# SmallStm.net
KiCad netlist of a schematic drawn in EasyEDA Pro
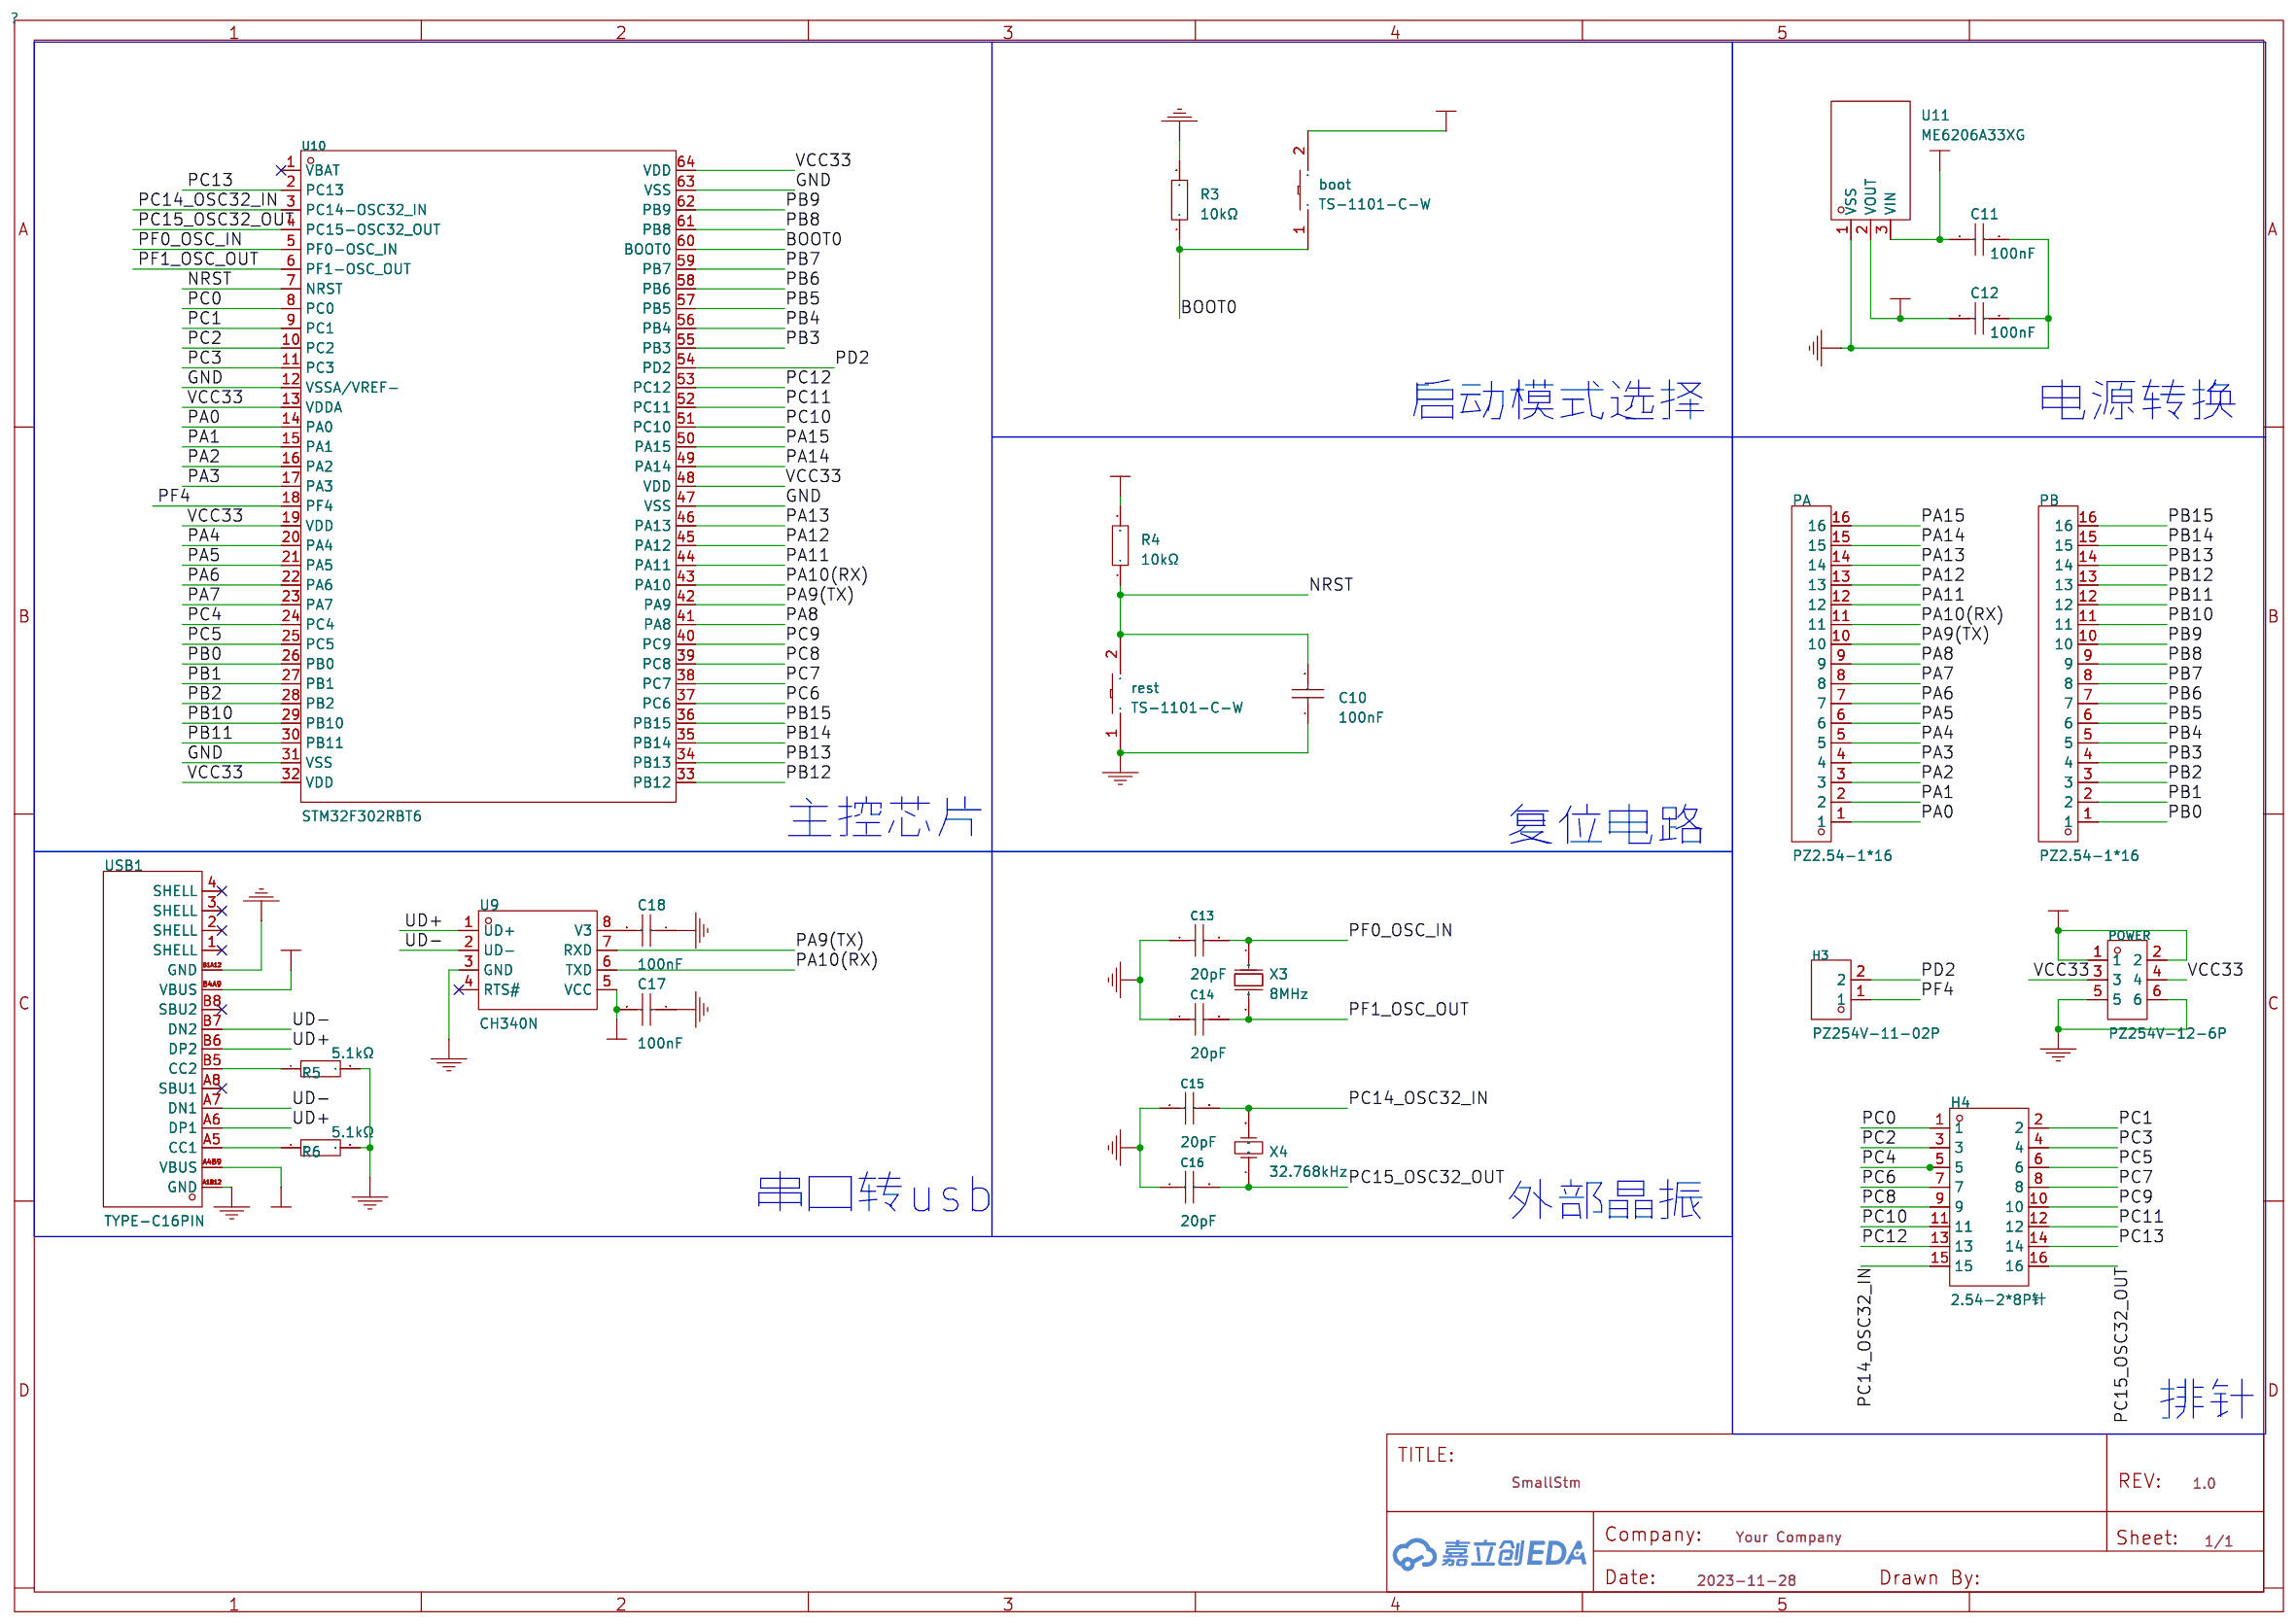
[diagram p0: schematic sheet]

(export (version "E")
  (design (tool "Eeschema 10.0.6"))
  (components
    (comp (ref "boot")
      (value "TS-1101-C-W")
      (footprint "easyedapro:SW-SMD_L6.0-W3.3-LS8.0")
      (description "电路结构:单刀单掷;带支架:否;触点电流:50mA;额定电压(AC):-;额定电压(DC):12V;额定功率:-;安装方式:立贴;绝缘电阻:-;带灯:无;作用力:260gf;机械寿命:5万次;")
      (fields (field (name "Manufacturer") "XKB Connectivity(中国星坤)"))
      (libsource (lib "easyedapro") (part "TS-1101-C-W"))
    )
    (comp (ref "C10")
      (value "100nF")
      (footprint "easyedapro:C0603")
      (description "容值:100nF;精度:±10%;额定电压:50V;材质(温度系数):X7R;")
      (fields (field (name "Manufacturer Part") "0603B104K500NT") (field (name "Manufacturer") "FH(风华)"))
      (libsource (lib "easyedapro") (part "0603B104K500NT"))
    )
    (comp (ref "C11")
      (value "100nF")
      (footprint "easyedapro:C0805")
      (description "容值:100nF;精度:±10%;额定电压:50V;材质(温度系数):X7R;")
      (fields (field (name "Manufacturer Part") "0805B104K500NT") (field (name "Manufacturer") "FH(风华)"))
      (libsource (lib "easyedapro") (part "0805B104K500NT"))
    )
    (comp (ref "C12")
      (value "100nF")
      (footprint "easyedapro:C0805")
      (description "容值:100nF;精度:±10%;额定电压:50V;材质(温度系数):X7R;")
      (fields (field (name "Manufacturer Part") "0805B104K500NT") (field (name "Manufacturer") "FH(风华)"))
      (libsource (lib "easyedapro") (part "0805B104K500NT"))
    )
    (comp (ref "C13")
      (value "20pF")
      (footprint "easyedapro:C0402")
      (description "容值:20pF;精度:±5%;额定电压:50V;材质(温度系数):C0G;")
      (fields (field (name "Manufacturer Part") "0402CG200J500NT") (field (name "Manufacturer") "FH(风华)"))
      (libsource (lib "easyedapro") (part "0402CG200J500NT"))
    )
    (comp (ref "C14")
      (value "20pF")
      (footprint "easyedapro:C0402")
      (description "容值:20pF;精度:±5%;额定电压:50V;材质(温度系数):C0G;")
      (fields (field (name "Manufacturer Part") "0402CG200J500NT") (field (name "Manufacturer") "FH(风华)"))
      (libsource (lib "easyedapro") (part "0402CG200J500NT"))
    )
    (comp (ref "C15")
      (value "20pF")
      (footprint "easyedapro:C0402")
      (description "容值:20pF;精度:±5%;额定电压:50V;材质(温度系数):C0G;")
      (fields (field (name "Manufacturer Part") "0402CG200J500NT") (field (name "Manufacturer") "FH(风华)"))
      (libsource (lib "easyedapro") (part "0402CG200J500NT"))
    )
    (comp (ref "C16")
      (value "20pF")
      (footprint "easyedapro:C0402")
      (description "容值:20pF;精度:±5%;额定电压:50V;材质(温度系数):C0G;")
      (fields (field (name "Manufacturer Part") "0402CG200J500NT") (field (name "Manufacturer") "FH(风华)"))
      (libsource (lib "easyedapro") (part "0402CG200J500NT"))
    )
    (comp (ref "C17")
      (value "100nF")
      (footprint "easyedapro:C0603")
      (description "容值:100nF;精度:±10%;额定电压:50V;材质(温度系数):X7R;")
      (fields (field (name "Manufacturer Part") "0603B104K500NT") (field (name "Manufacturer") "FH(风华)"))
      (libsource (lib "easyedapro") (part "0603B104K500NT"))
    )
    (comp (ref "C18")
      (value "100nF")
      (footprint "easyedapro:C0603")
      (description "容值:100nF;精度:±10%;额定电压:50V;材质(温度系数):X7R;")
      (fields (field (name "Manufacturer Part") "0603B104K500NT") (field (name "Manufacturer") "FH(风华)"))
      (libsource (lib "easyedapro") (part "0603B104K500NT"))
    )
    (comp (ref "H3")
      (value "PZ254V-11-02P")
      (footprint "easyedapro:HDR-TH_2P-P2.54-V-M")
      (fields (field (name "Manufacturer") "XFCN(兴飞)"))
      (libsource (lib "easyedapro") (part "PZ254V-11-02P"))
    )
    (comp (ref "H4")
      (value "2.54-2*8P针")
      (footprint "easyedapro:HDR-TH_16P-P2.54-V-M-R2-C8-S2.54")
      (description "圆针/方针:-;额定电流:-;额定电压:-;配合针长度:-;塑高:-;触头材质:-;")
      (fields (field (name "Manufacturer") "BOOMELE(博穆精密)"))
      (libsource (lib "easyedapro") (part "2.54-2*8P针"))
    )
    (comp (ref "PA")
      (value "PZ2.54-1*16")
      (footprint "easyedapro:HDR-TH_16P-P2.54-V-M")
      (fields (field (name "Manufacturer") "ZHOURI(洲日)"))
      (libsource (lib "easyedapro") (part "PZ2.54-1*16"))
    )
    (comp (ref "PB")
      (value "PZ2.54-1*16")
      (footprint "easyedapro:HDR-TH_16P-P2.54-V-M")
      (fields (field (name "Manufacturer") "ZHOURI(洲日)"))
      (libsource (lib "easyedapro") (part "PZ2.54-1*16"))
    )
    (comp (ref "POWER")
      (value "PZ254V-12-6P")
      (footprint "easyedapro:HDR-TH_6P-P2.54-V-M-R2-C3-S2.54")
      (fields (field (name "Manufacturer") "XFCN(兴飞)"))
      (libsource (lib "easyedapro") (part "PZ254V-12-6P"))
    )
    (comp (ref "R3")
      (value "10kΩ")
      (footprint "easyedapro:R0603")
      (description "阻值:10kΩ;精度:±1%;功率:100mW;温度系数:±100ppm/°C;电阻类型:厚膜电阻;")
      (fields
        (field (name "Manufacturer Part") "0603WAF1002T5E")
        (field (name "Manufacturer") "UNI-ROYAL(厚声)")
      )
      (libsource (lib "easyedapro") (part "0603WAF1002T5E"))
    )
    (comp (ref "R4")
      (value "10kΩ")
      (footprint "easyedapro:R0603")
      (description "阻值:10kΩ;精度:±1%;功率:100mW;温度系数:±100ppm/°C;电阻类型:厚膜电阻;")
      (fields
        (field (name "Manufacturer Part") "0603WAF1002T5E")
        (field (name "Manufacturer") "UNI-ROYAL(厚声)")
      )
      (libsource (lib "easyedapro") (part "0603WAF1002T5E"))
    )
    (comp (ref "R5")
      (value "5.1kΩ")
      (footprint "easyedapro:R0603")
      (description "阻值:5.1kΩ;精度:±1%;功率:100mW;温度系数:±100ppm/°C;电阻类型:厚膜电阻;")
      (fields
        (field (name "Manufacturer Part") "0603WAF5101T5E")
        (field (name "Manufacturer") "UNI-ROYAL(厚声)")
      )
      (libsource (lib "easyedapro") (part "0603WAF5101T5E"))
    )
    (comp (ref "R6")
      (value "5.1kΩ")
      (footprint "easyedapro:R0603")
      (description "阻值:5.1kΩ;精度:±1%;功率:100mW;温度系数:±100ppm/°C;电阻类型:厚膜电阻;")
      (fields
        (field (name "Manufacturer Part") "0603WAF5101T5E")
        (field (name "Manufacturer") "UNI-ROYAL(厚声)")
      )
      (libsource (lib "easyedapro") (part "0603WAF5101T5E"))
    )
    (comp (ref "rest")
      (value "TS-1101-C-W")
      (footprint "easyedapro:SW-SMD_L6.0-W3.3-LS8.0")
      (description "电路结构:单刀单掷;带支架:否;触点电流:50mA;额定电压(AC):-;额定电压(DC):12V;额定功率:-;安装方式:立贴;绝缘电阻:-;带灯:无;作用力:260gf;机械寿命:5万次;")
      (fields (field (name "Manufacturer") "XKB Connectivity(中国星坤)"))
      (libsource (lib "easyedapro") (part "TS-1101-C-W"))
    )
    (comp (ref "U9")
      (value "CH340N")
      (footprint "easyedapro:SOP-8_L4.9-W3.9-P1.27-LS6.0-BL")
      (fields (field (name "Manufacturer") "WCH(南京沁恒)"))
      (libsource (lib "easyedapro") (part "CH340N_C2977777"))
    )
    (comp (ref "U10")
      (value "STM32F302RBT6")
      (footprint "easyedapro:LQFP-64_L10.0-W10.0-P0.50-LS12.0-BL")
      (fields (field (name "Manufacturer") "ST(意法半导体)"))
      (libsource (lib "easyedapro") (part "STM32F302RBT6"))
    )
    (comp (ref "U11")
      (value "ME6206A33XG")
      (footprint "easyedapro:SOT-23-3_L2.9-W1.6-P1.90-LS2.8-BR")
      (description "输出类型:固定;输出极性:正;最大输入电压:6V;输出电压:3.3V;输出电流:300mA;电源纹波抑制比(PSRR):50dB@(1kHz);")
      (fields (field (name "Manufacturer") "MICRONE(南京微盟)"))
      (libsource (lib "easyedapro") (part "ME6206A33XG"))
    )
    (comp (ref "USB1")
      (value "TYPE-C16PIN")
      (footprint "easyedapro:USB-C-SMD_TYPE-C16PIN")
      (description "连接器类型:Type-C;标准:-;公母:母;触点数量:16P;端口数量:1;安装方式:卧贴;额定电流 - 电源:3A;工作温度范围:-40°C~+85°C;")
      (fields (field (name "Manufacturer") "SHOU HAN(首韩)"))
      (libsource (lib "easyedapro") (part "TYPE-C16PIN"))
    )
    (comp (ref "X3")
      (value "8MHz")
      (footprint "easyedapro:CRYSTAL-SMD_L11.5-W4.8-LS12.7")
      (description "频率:8MHz;负载电容:20pF;频率公差:±20ppm;")
      (fields (field (name "Manufacturer Part") "X49SM8MSD2SC") (field (name "Manufacturer") "YXC(扬兴晶振)"))
      (libsource (lib "easyedapro") (part "X49SM8MSD2SC"))
    )
    (comp (ref "X4")
      (value "32.768kHz")
      (footprint "easyedapro:OSC-TH_BD3.1-P0.8-D0.3")
      (description "频率:32.768kHz;负载电容:12.5pF;频率公差:±10ppm;")
      (fields (field (name "Manufacturer Part") "X308032768KGB2SC") (field (name "Manufacturer") "YXC(扬兴晶振)"))
      (libsource (lib "easyedapro") (part "X308032768KGB2SC"))
    )
  )
  (nets
    (net (code "1") (name "/BOOT0") (class "Default")
      (node (ref "R3") (pin "1") (pinfunction "1_1") (pintype "input"))
      (node (ref "U10") (pin "60") (pinfunction "BOOT0_60") (pintype "input"))
      (node (ref "boot") (pin "1") (pinfunction "1_1") (pintype "unspecified"))
    )
    (net (code "2") (name "/NRST") (class "Default")
      (node (ref "C10") (pin "2") (pinfunction "2_2") (pintype "input"))
      (node (ref "R4") (pin "1") (pinfunction "1_1") (pintype "input"))
      (node (ref "U10") (pin "7") (pinfunction "NRST_7") (pintype "input"))
      (node (ref "rest") (pin "2") (pinfunction "2_2") (pintype "unspecified"))
    )
    (net (code "3") (name "/PA0") (class "Default")
      (node (ref "PA") (pin "1") (pinfunction "1_1") (pintype "input"))
      (node (ref "U10") (pin "14") (pinfunction "PA0_14") (pintype "input"))
    )
    (net (code "4") (name "/PA1") (class "Default")
      (node (ref "PA") (pin "2") (pinfunction "2_2") (pintype "input"))
      (node (ref "U10") (pin "15") (pinfunction "PA1_15") (pintype "input"))
    )
    (net (code "5") (name "/PA2") (class "Default")
      (node (ref "PA") (pin "3") (pinfunction "3_3") (pintype "input"))
      (node (ref "U10") (pin "16") (pinfunction "PA2_16") (pintype "input"))
    )
    (net (code "6") (name "/PA3") (class "Default")
      (node (ref "PA") (pin "4") (pinfunction "4_4") (pintype "input"))
      (node (ref "U10") (pin "17") (pinfunction "PA3_17") (pintype "input"))
    )
    (net (code "7") (name "/PA4") (class "Default")
      (node (ref "PA") (pin "5") (pinfunction "5_5") (pintype "input"))
      (node (ref "U10") (pin "20") (pinfunction "PA4_20") (pintype "input"))
    )
    (net (code "8") (name "/PA5") (class "Default")
      (node (ref "PA") (pin "6") (pinfunction "6_6") (pintype "input"))
      (node (ref "U10") (pin "21") (pinfunction "PA5_21") (pintype "input"))
    )
    (net (code "9") (name "/PA6") (class "Default")
      (node (ref "PA") (pin "7") (pinfunction "7_7") (pintype "input"))
      (node (ref "U10") (pin "22") (pinfunction "PA6_22") (pintype "input"))
    )
    (net (code "10") (name "/PA7") (class "Default")
      (node (ref "PA") (pin "8") (pinfunction "8_8") (pintype "input"))
      (node (ref "U10") (pin "23") (pinfunction "PA7_23") (pintype "input"))
    )
    (net (code "11") (name "/PA8") (class "Default")
      (node (ref "PA") (pin "9") (pinfunction "9_9") (pintype "input"))
      (node (ref "U10") (pin "41") (pinfunction "PA8_41") (pintype "input"))
    )
    (net (code "12") (name "/PA9(TX)") (class "Default")
      (node (ref "PA") (pin "10") (pinfunction "10_10") (pintype "input"))
      (node (ref "U10") (pin "42") (pinfunction "PA9_42") (pintype "input"))
      (node (ref "U9") (pin "7") (pinfunction "RXD_7") (pintype "unspecified"))
    )
    (net (code "13") (name "/PA10(RX)") (class "Default")
      (node (ref "PA") (pin "11") (pinfunction "11_11") (pintype "input"))
      (node (ref "U10") (pin "43") (pinfunction "PA10_43") (pintype "input"))
      (node (ref "U9") (pin "6") (pinfunction "TXD_6") (pintype "unspecified"))
    )
    (net (code "14") (name "/PA11") (class "Default")
      (node (ref "PA") (pin "12") (pinfunction "12_12") (pintype "input"))
      (node (ref "U10") (pin "44") (pinfunction "PA11_44") (pintype "input"))
    )
    (net (code "15") (name "/PA12") (class "Default")
      (node (ref "PA") (pin "13") (pinfunction "13_13") (pintype "input"))
      (node (ref "U10") (pin "45") (pinfunction "PA12_45") (pintype "input"))
    )
    (net (code "16") (name "/PA13") (class "Default")
      (node (ref "PA") (pin "14") (pinfunction "14_14") (pintype "input"))
      (node (ref "U10") (pin "46") (pinfunction "PA13_46") (pintype "input"))
    )
    (net (code "17") (name "/PA14") (class "Default")
      (node (ref "PA") (pin "15") (pinfunction "15_15") (pintype "input"))
      (node (ref "U10") (pin "49") (pinfunction "PA14_49") (pintype "input"))
    )
    (net (code "18") (name "/PA15") (class "Default")
      (node (ref "PA") (pin "16") (pinfunction "16_16") (pintype "input"))
      (node (ref "U10") (pin "50") (pinfunction "PA15_50") (pintype "input"))
    )
    (net (code "19") (name "/PB0") (class "Default")
      (node (ref "PB") (pin "1") (pinfunction "1_1") (pintype "input"))
      (node (ref "U10") (pin "26") (pinfunction "PB0_26") (pintype "input"))
    )
    (net (code "20") (name "/PB1") (class "Default")
      (node (ref "PB") (pin "2") (pinfunction "2_2") (pintype "input"))
      (node (ref "U10") (pin "27") (pinfunction "PB1_27") (pintype "input"))
    )
    (net (code "21") (name "/PB2") (class "Default")
      (node (ref "PB") (pin "3") (pinfunction "3_3") (pintype "input"))
      (node (ref "U10") (pin "28") (pinfunction "PB2_28") (pintype "input"))
    )
    (net (code "22") (name "/PB3") (class "Default")
      (node (ref "PB") (pin "4") (pinfunction "4_4") (pintype "input"))
      (node (ref "U10") (pin "55") (pinfunction "PB3_55") (pintype "input"))
    )
    (net (code "23") (name "/PB4") (class "Default")
      (node (ref "PB") (pin "5") (pinfunction "5_5") (pintype "input"))
      (node (ref "U10") (pin "56") (pinfunction "PB4_56") (pintype "input"))
    )
    (net (code "24") (name "/PB5") (class "Default")
      (node (ref "PB") (pin "6") (pinfunction "6_6") (pintype "input"))
      (node (ref "U10") (pin "57") (pinfunction "PB5_57") (pintype "input"))
    )
    (net (code "25") (name "/PB6") (class "Default")
      (node (ref "PB") (pin "7") (pinfunction "7_7") (pintype "input"))
      (node (ref "U10") (pin "58") (pinfunction "PB6_58") (pintype "input"))
    )
    (net (code "26") (name "/PB7") (class "Default")
      (node (ref "PB") (pin "8") (pinfunction "8_8") (pintype "input"))
      (node (ref "U10") (pin "59") (pinfunction "PB7_59") (pintype "input"))
    )
    (net (code "27") (name "/PB8") (class "Default")
      (node (ref "PB") (pin "9") (pinfunction "9_9") (pintype "input"))
      (node (ref "U10") (pin "61") (pinfunction "PB8_61") (pintype "input"))
    )
    (net (code "28") (name "/PB9") (class "Default")
      (node (ref "PB") (pin "10") (pinfunction "10_10") (pintype "input"))
      (node (ref "U10") (pin "62") (pinfunction "PB9_62") (pintype "input"))
    )
    (net (code "29") (name "/PB10") (class "Default")
      (node (ref "PB") (pin "11") (pinfunction "11_11") (pintype "input"))
      (node (ref "U10") (pin "29") (pinfunction "PB10_29") (pintype "input"))
    )
    (net (code "30") (name "/PB11") (class "Default")
      (node (ref "PB") (pin "12") (pinfunction "12_12") (pintype "input"))
      (node (ref "U10") (pin "30") (pinfunction "PB11_30") (pintype "input"))
    )
    (net (code "31") (name "/PB12") (class "Default")
      (node (ref "PB") (pin "13") (pinfunction "13_13") (pintype "input"))
      (node (ref "U10") (pin "33") (pinfunction "PB12_33") (pintype "input"))
    )
    (net (code "32") (name "/PB13") (class "Default")
      (node (ref "PB") (pin "14") (pinfunction "14_14") (pintype "input"))
      (node (ref "U10") (pin "34") (pinfunction "PB13_34") (pintype "input"))
    )
    (net (code "33") (name "/PB14") (class "Default")
      (node (ref "PB") (pin "15") (pinfunction "15_15") (pintype "input"))
      (node (ref "U10") (pin "35") (pinfunction "PB14_35") (pintype "input"))
    )
    (net (code "34") (name "/PB15") (class "Default")
      (node (ref "PB") (pin "16") (pinfunction "16_16") (pintype "input"))
      (node (ref "U10") (pin "36") (pinfunction "PB15_36") (pintype "input"))
    )
    (net (code "35") (name "/PC0") (class "Default")
      (node (ref "H4") (pin "1") (pinfunction "1_1") (pintype "input"))
      (node (ref "U10") (pin "8") (pinfunction "PC0_8") (pintype "input"))
    )
    (net (code "36") (name "/PC1") (class "Default")
      (node (ref "H4") (pin "2") (pinfunction "2_2") (pintype "input"))
      (node (ref "U10") (pin "9") (pinfunction "PC1_9") (pintype "input"))
    )
    (net (code "37") (name "/PC2") (class "Default")
      (node (ref "H4") (pin "3") (pinfunction "3_3") (pintype "input"))
      (node (ref "U10") (pin "10") (pinfunction "PC2_10") (pintype "input"))
    )
    (net (code "38") (name "/PC3") (class "Default")
      (node (ref "H4") (pin "4") (pinfunction "4_4") (pintype "input"))
      (node (ref "U10") (pin "11") (pinfunction "PC3_11") (pintype "input"))
    )
    (net (code "39") (name "/PC4") (class "Default")
      (node (ref "H4") (pin "5") (pinfunction "5_5") (pintype "input"))
      (node (ref "U10") (pin "24") (pinfunction "PC4_24") (pintype "input"))
    )
    (net (code "40") (name "/PC5") (class "Default")
      (node (ref "H4") (pin "6") (pinfunction "6_6") (pintype "input"))
      (node (ref "U10") (pin "25") (pinfunction "PC5_25") (pintype "input"))
    )
    (net (code "41") (name "/PC6") (class "Default")
      (node (ref "H4") (pin "7") (pinfunction "7_7") (pintype "input"))
      (node (ref "U10") (pin "37") (pinfunction "PC6_37") (pintype "input"))
    )
    (net (code "42") (name "/PC7") (class "Default")
      (node (ref "H4") (pin "8") (pinfunction "8_8") (pintype "input"))
      (node (ref "U10") (pin "38") (pinfunction "PC7_38") (pintype "input"))
    )
    (net (code "43") (name "/PC8") (class "Default")
      (node (ref "H4") (pin "9") (pinfunction "9_9") (pintype "input"))
      (node (ref "U10") (pin "39") (pinfunction "PC8_39") (pintype "input"))
    )
    (net (code "44") (name "/PC9") (class "Default")
      (node (ref "H4") (pin "10") (pinfunction "10_10") (pintype "input"))
      (node (ref "U10") (pin "40") (pinfunction "PC9_40") (pintype "input"))
    )
    (net (code "45") (name "/PC10") (class "Default")
      (node (ref "H4") (pin "11") (pinfunction "11_11") (pintype "input"))
      (node (ref "U10") (pin "51") (pinfunction "PC10_51") (pintype "input"))
    )
    (net (code "46") (name "/PC11") (class "Default")
      (node (ref "H4") (pin "12") (pinfunction "12_12") (pintype "input"))
      (node (ref "U10") (pin "52") (pinfunction "PC11_52") (pintype "input"))
    )
    (net (code "47") (name "/PC12") (class "Default")
      (node (ref "H4") (pin "13") (pinfunction "13_13") (pintype "input"))
      (node (ref "U10") (pin "53") (pinfunction "PC12_53") (pintype "input"))
    )
    (net (code "48") (name "/PC13") (class "Default")
      (node (ref "H4") (pin "14") (pinfunction "14_14") (pintype "input"))
      (node (ref "U10") (pin "2") (pinfunction "PC13_2") (pintype "input"))
    )
    (net (code "49") (name "/PC14_OSC32_IN") (class "Default")
      (node (ref "C15") (pin "2") (pinfunction "2_2") (pintype "input"))
      (node (ref "H4") (pin "15") (pinfunction "15_15") (pintype "input"))
      (node (ref "U10") (pin "3") (pinfunction "PC14-OSC32_IN_3") (pintype "input"))
      (node (ref "X4") (pin "2") (pinfunction "OSC2_2") (pintype "unspecified"))
    )
    (net (code "50") (name "/PC15_OSC32_OUT") (class "Default")
      (node (ref "C16") (pin "2") (pinfunction "2_2") (pintype "input"))
      (node (ref "H4") (pin "16") (pinfunction "16_16") (pintype "input"))
      (node (ref "U10") (pin "4") (pinfunction "PC15-OSC32_OUT_4") (pintype "input"))
      (node (ref "X4") (pin "1") (pinfunction "OSC1_1") (pintype "unspecified"))
    )
    (net (code "51") (name "/PD2") (class "Default")
      (node (ref "H3") (pin "2") (pinfunction "2_2") (pintype "input"))
      (node (ref "U10") (pin "54") (pinfunction "PD2_54") (pintype "input"))
    )
    (net (code "52") (name "/PF0_OSC_IN") (class "Default")
      (node (ref "C13") (pin "2") (pinfunction "2_2") (pintype "input"))
      (node (ref "U10") (pin "5") (pinfunction "PF0-OSC_IN_5") (pintype "input"))
      (node (ref "X3") (pin "1") (pinfunction "OSC1_1") (pintype "input"))
    )
    (net (code "53") (name "/PF1_OSC_OUT") (class "Default")
      (node (ref "C14") (pin "2") (pinfunction "2_2") (pintype "input"))
      (node (ref "U10") (pin "6") (pinfunction "PF1-OSC_OUT_6") (pintype "input"))
      (node (ref "X3") (pin "2") (pinfunction "OSC2_2") (pintype "input"))
    )
    (net (code "54") (name "/PF4") (class "Default")
      (node (ref "H3") (pin "1") (pinfunction "1_1") (pintype "input"))
      (node (ref "U10") (pin "18") (pinfunction "PF4_18") (pintype "input"))
    )
    (net (code "55") (name "/UD+") (class "Default")
      (node (ref "U9") (pin "1") (pinfunction "UD+_1") (pintype "unspecified"))
      (node (ref "USB1") (pin "A6") (pinfunction "DP1_A6") (pintype "unspecified"))
      (node (ref "USB1") (pin "B6") (pinfunction "DP2_B6") (pintype "unspecified"))
    )
    (net (code "56") (name "/UD-") (class "Default")
      (node (ref "U9") (pin "2") (pinfunction "UD-_2") (pintype "unspecified"))
      (node (ref "USB1") (pin "A7") (pinfunction "DN1_A7") (pintype "unspecified"))
      (node (ref "USB1") (pin "B7") (pinfunction "DN2_B7") (pintype "unspecified"))
    )
    (net (code "57") (name "GND") (class "Default")
      (node (ref "C10") (pin "1") (pinfunction "1_1") (pintype "input"))
      (node (ref "C11") (pin "2") (pinfunction "2_2") (pintype "input"))
      (node (ref "C12") (pin "2") (pinfunction "2_2") (pintype "input"))
      (node (ref "C13") (pin "1") (pinfunction "1_1") (pintype "input"))
      (node (ref "C14") (pin "1") (pinfunction "1_1") (pintype "input"))
      (node (ref "C15") (pin "1") (pinfunction "1_1") (pintype "input"))
      (node (ref "C16") (pin "1") (pinfunction "1_1") (pintype "input"))
      (node (ref "C17") (pin "1") (pinfunction "1_1") (pintype "input"))
      (node (ref "C18") (pin "1") (pinfunction "1_1") (pintype "input"))
      (node (ref "POWER") (pin "5") (pinfunction "5_5") (pintype "input"))
      (node (ref "POWER") (pin "6") (pinfunction "6_6") (pintype "input"))
      (node (ref "R3") (pin "2") (pinfunction "2_2") (pintype "input"))
      (node (ref "R5") (pin "2") (pinfunction "2_2") (pintype "input"))
      (node (ref "R6") (pin "2") (pinfunction "2_2") (pintype "input"))
      (node (ref "U10") (pin "12") (pinfunction "VSSA/VREF-_12") (pintype "input"))
      (node (ref "U10") (pin "31") (pinfunction "VSS_31") (pintype "input"))
      (node (ref "U10") (pin "47") (pinfunction "VSS_47") (pintype "input"))
      (node (ref "U10") (pin "63") (pinfunction "VSS_63") (pintype "input"))
      (node (ref "U11") (pin "1") (pinfunction "VSS_1") (pintype "input"))
      (node (ref "U9") (pin "3") (pinfunction "GND_3") (pintype "unspecified"))
      (node (ref "USB1") (pin "A1B12") (pinfunction "GND_A1B12") (pintype "unspecified"))
      (node (ref "USB1") (pin "B1A12") (pinfunction "GND_B1A12") (pintype "unspecified"))
      (node (ref "rest") (pin "1") (pinfunction "1_1") (pintype "unspecified"))
    )
    (net (code "58") (name "Net-(U9-V3)") (class "Default")
      (node (ref "C18") (pin "2") (pinfunction "2_2") (pintype "input"))
      (node (ref "U9") (pin "8") (pinfunction "V3_8") (pintype "unspecified"))
    )
    (net (code "59") (name "Net-(USB1-CC1)") (class "Default")
      (node (ref "R6") (pin "1") (pinfunction "1_1") (pintype "input"))
      (node (ref "USB1") (pin "A5") (pinfunction "CC1_A5") (pintype "unspecified"))
    )
    (net (code "60") (name "Net-(USB1-CC2)") (class "Default")
      (node (ref "R5") (pin "1") (pinfunction "1_1") (pintype "input"))
      (node (ref "USB1") (pin "B5") (pinfunction "CC2_B5") (pintype "unspecified"))
    )
    (net (code "61") (name "VCC5") (class "Default")
      (node (ref "C11") (pin "1") (pinfunction "1_1") (pintype "input"))
      (node (ref "C17") (pin "2") (pinfunction "2_2") (pintype "input"))
      (node (ref "POWER") (pin "1") (pinfunction "1_1") (pintype "input"))
      (node (ref "POWER") (pin "2") (pinfunction "2_2") (pintype "input"))
      (node (ref "U11") (pin "3") (pinfunction "VIN_3") (pintype "input"))
      (node (ref "U9") (pin "5") (pinfunction "VCC_5") (pintype "unspecified"))
      (node (ref "USB1") (pin "A4B9") (pinfunction "VBUS_A4B9") (pintype "unspecified"))
      (node (ref "USB1") (pin "B4A9") (pinfunction "VBUS_B4A9") (pintype "unspecified"))
    )
    (net (code "62") (name "VCC33") (class "Default")
      (node (ref "C12") (pin "1") (pinfunction "1_1") (pintype "input"))
      (node (ref "POWER") (pin "3") (pinfunction "3_3") (pintype "input"))
      (node (ref "POWER") (pin "4") (pinfunction "4_4") (pintype "input"))
      (node (ref "R4") (pin "2") (pinfunction "2_2") (pintype "input"))
      (node (ref "U10") (pin "13") (pinfunction "VDDA_13") (pintype "input"))
      (node (ref "U10") (pin "19") (pinfunction "VDD_19") (pintype "input"))
      (node (ref "U10") (pin "32") (pinfunction "VDD_32") (pintype "input"))
      (node (ref "U10") (pin "48") (pinfunction "VDD_48") (pintype "input"))
      (node (ref "U10") (pin "64") (pinfunction "VDD_64") (pintype "input"))
      (node (ref "U11") (pin "2") (pinfunction "VOUT_2") (pintype "input"))
      (node (ref "boot") (pin "2") (pinfunction "2_2") (pintype "unspecified"))
    )
    (net (code "63") (name "unconnected-(U9-RTS#-Pad4)") (class "Default")
      (node (ref "U9") (pin "4") (pinfunction "RTS#_4") (pintype "unspecified+no_connect"))
    )
    (net (code "64") (name "unconnected-(U10-VBAT-Pad1)") (class "Default")
      (node (ref "U10") (pin "1") (pinfunction "VBAT_1") (pintype "input+no_connect"))
    )
    (net (code "65") (name "unconnected-(USB1-SBU1-PadA8)") (class "Default")
      (node (ref "USB1") (pin "A8") (pinfunction "SBU1_A8") (pintype "unspecified+no_connect"))
    )
    (net (code "66") (name "unconnected-(USB1-SBU2-PadB8)") (class "Default")
      (node (ref "USB1") (pin "B8") (pinfunction "SBU2_B8") (pintype "unspecified+no_connect"))
    )
    (net (code "67") (name "unconnected-(USB1-SHELL-Pad1)") (class "Default")
      (node (ref "USB1") (pin "1") (pinfunction "SHELL_1") (pintype "unspecified+no_connect"))
    )
    (net (code "68") (name "unconnected-(USB1-SHELL-Pad2)") (class "Default")
      (node (ref "USB1") (pin "2") (pinfunction "SHELL_2") (pintype "unspecified+no_connect"))
    )
    (net (code "69") (name "unconnected-(USB1-SHELL-Pad3)") (class "Default")
      (node (ref "USB1") (pin "3") (pinfunction "SHELL_3") (pintype "unspecified+no_connect"))
    )
    (net (code "70") (name "unconnected-(USB1-SHELL-Pad4)") (class "Default")
      (node (ref "USB1") (pin "4") (pinfunction "SHELL_4") (pintype "unspecified+no_connect"))
    )
  )
)
